# LCD_Module.net
KiCad netlist of a schematic drawn in Altium Designer
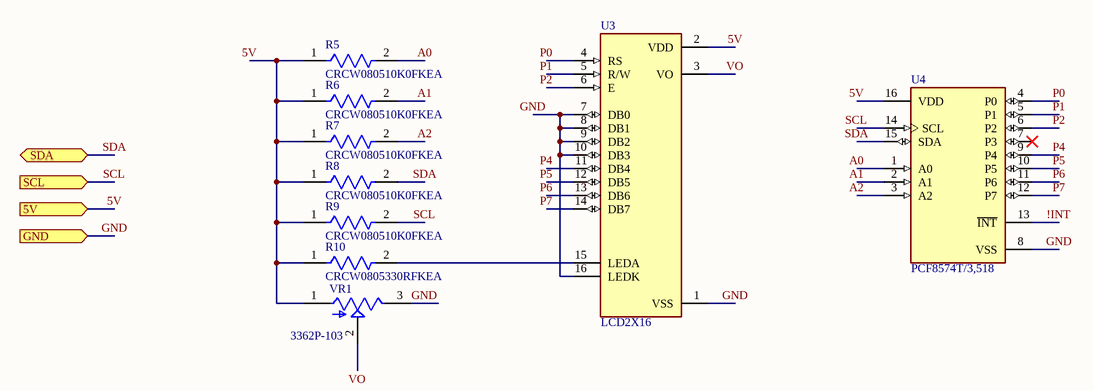
[diagram p0: LCD_Module.SchDoc]

(export (version "E")
  (design (tool "Eeschema 10.0.6"))
  (components
    (comp (ref "R5")
      (value "CRCW080510K0FKEA")
      (footprint "FP-CRCW0805-e3-IPC_A")
      (description "RES Thick Film, 10kΩ, 1%, 0.125W, 100ppm/°C, 0805")
      (fields (field (name "TOLERANCE") "1%"))
      (libsource (lib "Altium Content Vault") (part "1029c3af85768c4190bb7ad29bc67b5"))
    )
    (comp (ref "R6")
      (value "CRCW080510K0FKEA")
      (footprint "FP-CRCW0805-e3-IPC_A")
      (description "RES Thick Film, 10kΩ, 1%, 0.125W, 100ppm/°C, 0805")
      (fields (field (name "TOLERANCE") "1%"))
      (libsource (lib "Altium Content Vault") (part "1029c3af85768c4190bb7ad29bc67b5"))
    )
    (comp (ref "R7")
      (value "CRCW080510K0FKEA")
      (footprint "FP-CRCW0805-e3-IPC_A")
      (description "RES Thick Film, 10kΩ, 1%, 0.125W, 100ppm/°C, 0805")
      (fields (field (name "TOLERANCE") "1%"))
      (libsource (lib "Altium Content Vault") (part "1029c3af85768c4190bb7ad29bc67b5"))
    )
    (comp (ref "R8")
      (value "CRCW080510K0FKEA")
      (footprint "FP-CRCW0805-e3-IPC_A")
      (description "RES Thick Film, 10kΩ, 1%, 0.125W, 100ppm/°C, 0805")
      (fields (field (name "TOLERANCE") "1%"))
      (libsource (lib "Altium Content Vault") (part "1029c3af85768c4190bb7ad29bc67b5"))
    )
    (comp (ref "R9")
      (value "CRCW080510K0FKEA")
      (footprint "FP-CRCW0805-e3-IPC_A")
      (description "RES Thick Film, 10kΩ, 1%, 0.125W, 100ppm/°C, 0805")
      (fields (field (name "TOLERANCE") "1%"))
      (libsource (lib "Altium Content Vault") (part "1029c3af85768c4190bb7ad29bc67b5"))
    )
    (comp (ref "R10")
      (value "CRCW0805330RFKEA")
      (footprint "FP-CRCW0805-e3-MFG")
      (description "RES Thick Film, 330Ω, 1%, 0.125W, 100ppm/°C, 0805")
      (fields (field (name "TOLERANCE") "1%"))
      (libsource (lib "Altium Content Vault") (part "1029c3af85768c4190bb7ad29bc67b5"))
    )
    (comp (ref "U3")
      (value "LCD2X16")
      (footprint "LCD_LCD2X16")
      (description "Display; Display: LCD 2x16 characters (blue backlight)")
      (fields (field (name "MF") "mikroElektronika"))
      (libsource (lib "LCD2X16") (part "LCD2X16"))
    )
    (comp (ref "U4")
      (value "PCF8574T/3,518")
      (footprint "FP-SOT162-1-MFG")
      (description "IC I/O EXPANDER I2C 8B 16SOIC")
      (fields
        (field (name "MANUFACTURER") "NXP Semiconductors")
        (field (name "OCTOPART") "https://octopart.com/pcf8574t%2F3%2C518-nxp+semiconductors-10470852")
      )
      (libsource (lib "Altium Content Vault") (part "f7fde53ce59de981fb0b266a4e103eb"))
    )
    (comp (ref "VR1")
      (value "3362P-103")
      (footprint "TRIM_3362P-103")
      (libsource (lib "3362P-103") (part "3362P-103"))
    )
  )
  (nets
    (net (code "1") (name "/!INT") (class "Default")
      (node (ref "U4") (pin "13") (pinfunction "~{INT}_13") (pintype "open_collector"))
    )
    (net (code "2") (name "/5V") (class "Default")
      (node (ref "R10") (pin "1") (pinfunction "1_1") (pintype "passive"))
      (node (ref "R5") (pin "1") (pinfunction "1_1") (pintype "passive"))
      (node (ref "R6") (pin "1") (pinfunction "1_1") (pintype "passive"))
      (node (ref "R7") (pin "1") (pinfunction "1_1") (pintype "passive"))
      (node (ref "R8") (pin "1") (pinfunction "1_1") (pintype "passive"))
      (node (ref "R9") (pin "1") (pinfunction "1_1") (pintype "passive"))
      (node (ref "U3") (pin "2") (pinfunction "VDD_2") (pintype "power_in"))
      (node (ref "U4") (pin "16") (pinfunction "VDD_16") (pintype "power_in"))
      (node (ref "VR1") (pin "1") (pinfunction "CCW_1") (pintype "passive"))
    )
    (net (code "3") (name "/A0") (class "Default")
      (node (ref "R5") (pin "2") (pinfunction "2_2") (pintype "passive"))
      (node (ref "U4") (pin "1") (pinfunction "A0_1") (pintype "input"))
    )
    (net (code "4") (name "/A1") (class "Default")
      (node (ref "R6") (pin "2") (pinfunction "2_2") (pintype "passive"))
      (node (ref "U4") (pin "2") (pinfunction "A1_2") (pintype "input"))
    )
    (net (code "5") (name "/A2") (class "Default")
      (node (ref "R7") (pin "2") (pinfunction "2_2") (pintype "passive"))
      (node (ref "U4") (pin "3") (pinfunction "A2_3") (pintype "input"))
    )
    (net (code "6") (name "/GND") (class "Default")
      (node (ref "U3") (pin "1") (pinfunction "VSS_1") (pintype "power_in"))
      (node (ref "U3") (pin "10") (pinfunction "DB3_10") (pintype "bidirectional"))
      (node (ref "U3") (pin "16") (pinfunction "LEDK_16") (pintype "passive"))
      (node (ref "U3") (pin "7") (pinfunction "DB0_7") (pintype "bidirectional"))
      (node (ref "U3") (pin "8") (pinfunction "DB1_8") (pintype "bidirectional"))
      (node (ref "U3") (pin "9") (pinfunction "DB2_9") (pintype "bidirectional"))
      (node (ref "U4") (pin "8") (pinfunction "VSS_8") (pintype "power_in"))
      (node (ref "VR1") (pin "3") (pinfunction "CW_3") (pintype "passive"))
    )
    (net (code "7") (name "/P0") (class "Default")
      (node (ref "U3") (pin "4") (pinfunction "RS_4") (pintype "input"))
      (node (ref "U4") (pin "4") (pinfunction "P0_4") (pintype "bidirectional"))
    )
    (net (code "8") (name "/P1") (class "Default")
      (node (ref "U3") (pin "5") (pinfunction "R/W_5") (pintype "input"))
      (node (ref "U4") (pin "5") (pinfunction "P1_5") (pintype "bidirectional"))
    )
    (net (code "9") (name "/P2") (class "Default")
      (node (ref "U3") (pin "6") (pinfunction "E_6") (pintype "input"))
      (node (ref "U4") (pin "6") (pinfunction "P2_6") (pintype "bidirectional"))
    )
    (net (code "10") (name "/P4") (class "Default")
      (node (ref "U3") (pin "11") (pinfunction "DB4_11") (pintype "bidirectional"))
      (node (ref "U4") (pin "9") (pinfunction "P4_9") (pintype "bidirectional"))
    )
    (net (code "11") (name "/P5") (class "Default")
      (node (ref "U3") (pin "12") (pinfunction "DB5_12") (pintype "bidirectional"))
      (node (ref "U4") (pin "10") (pinfunction "P5_10") (pintype "bidirectional"))
    )
    (net (code "12") (name "/P6") (class "Default")
      (node (ref "U3") (pin "13") (pinfunction "DB6_13") (pintype "bidirectional"))
      (node (ref "U4") (pin "11") (pinfunction "P6_11") (pintype "bidirectional"))
    )
    (net (code "13") (name "/P7") (class "Default")
      (node (ref "U3") (pin "14") (pinfunction "DB7_14") (pintype "bidirectional"))
      (node (ref "U4") (pin "12") (pinfunction "P7_12") (pintype "bidirectional"))
    )
    (net (code "14") (name "/SCL") (class "Default")
      (node (ref "R9") (pin "2") (pinfunction "2_2") (pintype "passive"))
      (node (ref "U4") (pin "14") (pinfunction "SCL_14") (pintype "input"))
    )
    (net (code "15") (name "/SDA") (class "Default")
      (node (ref "R8") (pin "2") (pinfunction "2_2") (pintype "passive"))
      (node (ref "U4") (pin "15") (pinfunction "SDA_15") (pintype "bidirectional"))
    )
    (net (code "16") (name "/VO") (class "Default")
      (node (ref "U3") (pin "3") (pinfunction "VO_3") (pintype "passive"))
      (node (ref "VR1") (pin "2") (pinfunction "WIPER_2") (pintype "passive"))
    )
    (net (code "17") (name "Net-(U3-LEDA)") (class "Default")
      (node (ref "R10") (pin "2") (pinfunction "2_2") (pintype "passive"))
      (node (ref "U3") (pin "15") (pinfunction "LEDA_15") (pintype "passive"))
    )
    (net (code "18") (name "unconnected-(U4-P3-Pad7)") (class "Default")
      (node (ref "U4") (pin "7") (pinfunction "P3_7") (pintype "bidirectional+no_connect"))
    )
  )
)
